# PC104.net
KiCad netlist of a schematic drawn in Altium Designer
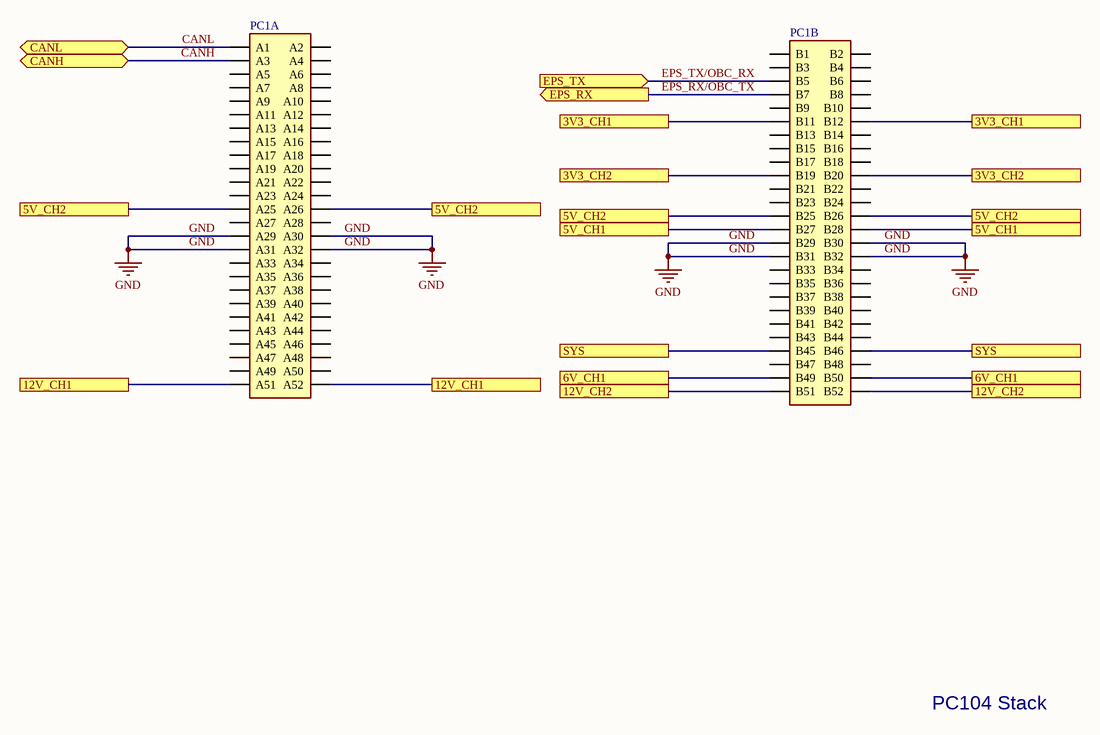
[diagram p0: PC104.SchDoc]

(export (version "E")
  (design (tool "Eeschema 10.0.6"))
  (components
    (comp (ref "PC1")
      (value "SSQ-126-21-G-D")
      (footprint "PC104 STACK HEADER")
      (description "PC104 stack header, 2.54mm 4x26positions")
      (fields (field (name "DISTRIBUTOR PART NUMBER") "SSQ-126-21-G-D-ND"))
      (libsource (lib "Ahristi_Library") (part "PC104"))
    )
  )
  (nets
    (net (code "1") (name "/3V3_CH1") (class "Default")
      (node (ref "PC1") (pin "B11") (pinfunction "B11_B11") (pintype "passive"))
      (node (ref "PC1") (pin "B12") (pinfunction "B12_B12") (pintype "passive"))
    )
    (net (code "2") (name "/3V3_CH2") (class "Default")
      (node (ref "PC1") (pin "B19") (pinfunction "B19_B19") (pintype "passive"))
      (node (ref "PC1") (pin "B20") (pinfunction "B20_B20") (pintype "passive"))
    )
    (net (code "3") (name "/5V_CH1") (class "Default")
      (node (ref "PC1") (pin "B27") (pinfunction "B27_B27") (pintype "passive"))
      (node (ref "PC1") (pin "B28") (pinfunction "B28_B28") (pintype "passive"))
    )
    (net (code "4") (name "/5V_CH2") (class "Default")
      (node (ref "PC1") (pin "A25") (pinfunction "A25_A25") (pintype "passive"))
      (node (ref "PC1") (pin "A26") (pinfunction "A26_A26") (pintype "passive"))
      (node (ref "PC1") (pin "B25") (pinfunction "B25_B25") (pintype "passive"))
      (node (ref "PC1") (pin "B26") (pinfunction "B26_B26") (pintype "passive"))
    )
    (net (code "5") (name "/6V_CH1") (class "Default")
      (node (ref "PC1") (pin "B49") (pinfunction "B49_B49") (pintype "passive"))
      (node (ref "PC1") (pin "B50") (pinfunction "B50_B50") (pintype "passive"))
    )
    (net (code "6") (name "/12V_CH1") (class "Default")
      (node (ref "PC1") (pin "A51") (pinfunction "A51_A51") (pintype "passive"))
      (node (ref "PC1") (pin "A52") (pinfunction "A52_A52") (pintype "passive"))
    )
    (net (code "7") (name "/12V_CH2") (class "Default")
      (node (ref "PC1") (pin "B51") (pinfunction "B51_B51") (pintype "passive"))
      (node (ref "PC1") (pin "B52") (pinfunction "B52_B52") (pintype "passive"))
    )
    (net (code "8") (name "/CANH") (class "Default")
      (node (ref "PC1") (pin "A3") (pinfunction "A3_A3") (pintype "passive"))
    )
    (net (code "9") (name "/CANL") (class "Default")
      (node (ref "PC1") (pin "A1") (pinfunction "A1_A1") (pintype "passive"))
    )
    (net (code "10") (name "/EPS_RX{slash}OBC_TX") (class "Default")
      (node (ref "PC1") (pin "B7") (pinfunction "B7_B7") (pintype "passive"))
    )
    (net (code "11") (name "/EPS_TX{slash}OBC_RX") (class "Default")
      (node (ref "PC1") (pin "B5") (pinfunction "B5_B5") (pintype "passive"))
    )
    (net (code "12") (name "/SYS") (class "Default")
      (node (ref "PC1") (pin "B45") (pinfunction "B45_B45") (pintype "passive"))
      (node (ref "PC1") (pin "B46") (pinfunction "B46_B46") (pintype "passive"))
    )
    (net (code "13") (name "GND") (class "Default")
      (node (ref "PC1") (pin "A29") (pinfunction "A29_A29") (pintype "passive"))
      (node (ref "PC1") (pin "A30") (pinfunction "A30_A30") (pintype "passive"))
      (node (ref "PC1") (pin "A31") (pinfunction "A31_A31") (pintype "passive"))
      (node (ref "PC1") (pin "A32") (pinfunction "A32_A32") (pintype "passive"))
      (node (ref "PC1") (pin "B29") (pinfunction "B29_B29") (pintype "passive"))
      (node (ref "PC1") (pin "B30") (pinfunction "B30_B30") (pintype "passive"))
      (node (ref "PC1") (pin "B31") (pinfunction "B31_B31") (pintype "passive"))
      (node (ref "PC1") (pin "B32") (pinfunction "B32_B32") (pintype "passive"))
    )
    (net (code "14") (name "unconnected-(PC1-PadA2)") (class "Default")
      (node (ref "PC1") (pin "A2") (pinfunction "A2_A2") (pintype "passive"))
    )
    (net (code "15") (name "unconnected-(PC1-PadA4)") (class "Default")
      (node (ref "PC1") (pin "A4") (pinfunction "A4_A4") (pintype "passive"))
    )
    (net (code "16") (name "unconnected-(PC1-PadA5)") (class "Default")
      (node (ref "PC1") (pin "A5") (pinfunction "A5_A5") (pintype "passive"))
    )
    (net (code "17") (name "unconnected-(PC1-PadA6)") (class "Default")
      (node (ref "PC1") (pin "A6") (pinfunction "A6_A6") (pintype "passive"))
    )
    (net (code "18") (name "unconnected-(PC1-PadA7)") (class "Default")
      (node (ref "PC1") (pin "A7") (pinfunction "A7_A7") (pintype "passive"))
    )
    (net (code "19") (name "unconnected-(PC1-PadA8)") (class "Default")
      (node (ref "PC1") (pin "A8") (pinfunction "A8_A8") (pintype "passive"))
    )
    (net (code "20") (name "unconnected-(PC1-PadA9)") (class "Default")
      (node (ref "PC1") (pin "A9") (pinfunction "A9_A9") (pintype "passive"))
    )
    (net (code "21") (name "unconnected-(PC1-PadA10)") (class "Default")
      (node (ref "PC1") (pin "A10") (pinfunction "A10_A10") (pintype "passive"))
    )
    (net (code "22") (name "unconnected-(PC1-PadA11)") (class "Default")
      (node (ref "PC1") (pin "A11") (pinfunction "A11_A11") (pintype "passive"))
    )
    (net (code "23") (name "unconnected-(PC1-PadA12)") (class "Default")
      (node (ref "PC1") (pin "A12") (pinfunction "A12_A12") (pintype "passive"))
    )
    (net (code "24") (name "unconnected-(PC1-PadA13)") (class "Default")
      (node (ref "PC1") (pin "A13") (pinfunction "A13_A13") (pintype "passive"))
    )
    (net (code "25") (name "unconnected-(PC1-PadA14)") (class "Default")
      (node (ref "PC1") (pin "A14") (pinfunction "A14_A14") (pintype "passive"))
    )
    (net (code "26") (name "unconnected-(PC1-PadA15)") (class "Default")
      (node (ref "PC1") (pin "A15") (pinfunction "A15_A15") (pintype "passive"))
    )
    (net (code "27") (name "unconnected-(PC1-PadA16)") (class "Default")
      (node (ref "PC1") (pin "A16") (pinfunction "A16_A16") (pintype "passive"))
    )
    (net (code "28") (name "unconnected-(PC1-PadA17)") (class "Default")
      (node (ref "PC1") (pin "A17") (pinfunction "A17_A17") (pintype "passive"))
    )
    (net (code "29") (name "unconnected-(PC1-PadA18)") (class "Default")
      (node (ref "PC1") (pin "A18") (pinfunction "A18_A18") (pintype "passive"))
    )
    (net (code "30") (name "unconnected-(PC1-PadA19)") (class "Default")
      (node (ref "PC1") (pin "A19") (pinfunction "A19_A19") (pintype "passive"))
    )
    (net (code "31") (name "unconnected-(PC1-PadA20)") (class "Default")
      (node (ref "PC1") (pin "A20") (pinfunction "A20_A20") (pintype "passive"))
    )
    (net (code "32") (name "unconnected-(PC1-PadA21)") (class "Default")
      (node (ref "PC1") (pin "A21") (pinfunction "A21_A21") (pintype "passive"))
    )
    (net (code "33") (name "unconnected-(PC1-PadA22)") (class "Default")
      (node (ref "PC1") (pin "A22") (pinfunction "A22_A22") (pintype "passive"))
    )
    (net (code "34") (name "unconnected-(PC1-PadA23)") (class "Default")
      (node (ref "PC1") (pin "A23") (pinfunction "A23_A23") (pintype "passive"))
    )
    (net (code "35") (name "unconnected-(PC1-PadA24)") (class "Default")
      (node (ref "PC1") (pin "A24") (pinfunction "A24_A24") (pintype "passive"))
    )
    (net (code "36") (name "unconnected-(PC1-PadA27)") (class "Default")
      (node (ref "PC1") (pin "A27") (pinfunction "A27_A27") (pintype "passive"))
    )
    (net (code "37") (name "unconnected-(PC1-PadA28)") (class "Default")
      (node (ref "PC1") (pin "A28") (pinfunction "A28_A28") (pintype "passive"))
    )
    (net (code "38") (name "unconnected-(PC1-PadA33)") (class "Default")
      (node (ref "PC1") (pin "A33") (pinfunction "A33_A33") (pintype "passive"))
    )
    (net (code "39") (name "unconnected-(PC1-PadA34)") (class "Default")
      (node (ref "PC1") (pin "A34") (pinfunction "A34_A34") (pintype "passive"))
    )
    (net (code "40") (name "unconnected-(PC1-PadA35)") (class "Default")
      (node (ref "PC1") (pin "A35") (pinfunction "A35_A35") (pintype "passive"))
    )
    (net (code "41") (name "unconnected-(PC1-PadA36)") (class "Default")
      (node (ref "PC1") (pin "A36") (pinfunction "A36_A36") (pintype "passive"))
    )
    (net (code "42") (name "unconnected-(PC1-PadA37)") (class "Default")
      (node (ref "PC1") (pin "A37") (pinfunction "A37_A37") (pintype "passive"))
    )
    (net (code "43") (name "unconnected-(PC1-PadA38)") (class "Default")
      (node (ref "PC1") (pin "A38") (pinfunction "A38_A38") (pintype "passive"))
    )
    (net (code "44") (name "unconnected-(PC1-PadA39)") (class "Default")
      (node (ref "PC1") (pin "A39") (pinfunction "A39_A39") (pintype "passive"))
    )
    (net (code "45") (name "unconnected-(PC1-PadA40)") (class "Default")
      (node (ref "PC1") (pin "A40") (pinfunction "A40_A40") (pintype "passive"))
    )
    (net (code "46") (name "unconnected-(PC1-PadA41)") (class "Default")
      (node (ref "PC1") (pin "A41") (pinfunction "A41_A41") (pintype "passive"))
    )
    (net (code "47") (name "unconnected-(PC1-PadA42)") (class "Default")
      (node (ref "PC1") (pin "A42") (pinfunction "A42_A42") (pintype "passive"))
    )
    (net (code "48") (name "unconnected-(PC1-PadA43)") (class "Default")
      (node (ref "PC1") (pin "A43") (pinfunction "A43_A43") (pintype "passive"))
    )
    (net (code "49") (name "unconnected-(PC1-PadA44)") (class "Default")
      (node (ref "PC1") (pin "A44") (pinfunction "A44_A44") (pintype "passive"))
    )
    (net (code "50") (name "unconnected-(PC1-PadA45)") (class "Default")
      (node (ref "PC1") (pin "A45") (pinfunction "A45_A45") (pintype "passive"))
    )
    (net (code "51") (name "unconnected-(PC1-PadA46)") (class "Default")
      (node (ref "PC1") (pin "A46") (pinfunction "A46_A46") (pintype "passive"))
    )
    (net (code "52") (name "unconnected-(PC1-PadA47)") (class "Default")
      (node (ref "PC1") (pin "A47") (pinfunction "A47_A47") (pintype "passive"))
    )
    (net (code "53") (name "unconnected-(PC1-PadA48)") (class "Default")
      (node (ref "PC1") (pin "A48") (pinfunction "A48_A48") (pintype "passive"))
    )
    (net (code "54") (name "unconnected-(PC1-PadA49)") (class "Default")
      (node (ref "PC1") (pin "A49") (pinfunction "A49_A49") (pintype "passive"))
    )
    (net (code "55") (name "unconnected-(PC1-PadA50)") (class "Default")
      (node (ref "PC1") (pin "A50") (pinfunction "A50_A50") (pintype "passive"))
    )
    (net (code "56") (name "unconnected-(PC1-PadB1)") (class "Default")
      (node (ref "PC1") (pin "B1") (pinfunction "B1_B1") (pintype "passive"))
    )
    (net (code "57") (name "unconnected-(PC1-PadB2)") (class "Default")
      (node (ref "PC1") (pin "B2") (pinfunction "B2_B2") (pintype "passive"))
    )
    (net (code "58") (name "unconnected-(PC1-PadB3)") (class "Default")
      (node (ref "PC1") (pin "B3") (pinfunction "B3_B3") (pintype "passive"))
    )
    (net (code "59") (name "unconnected-(PC1-PadB4)") (class "Default")
      (node (ref "PC1") (pin "B4") (pinfunction "B4_B4") (pintype "passive"))
    )
    (net (code "60") (name "unconnected-(PC1-PadB6)") (class "Default")
      (node (ref "PC1") (pin "B6") (pinfunction "B6_B6") (pintype "passive"))
    )
    (net (code "61") (name "unconnected-(PC1-PadB8)") (class "Default")
      (node (ref "PC1") (pin "B8") (pinfunction "B8_B8") (pintype "passive"))
    )
    (net (code "62") (name "unconnected-(PC1-PadB9)") (class "Default")
      (node (ref "PC1") (pin "B9") (pinfunction "B9_B9") (pintype "passive"))
    )
    (net (code "63") (name "unconnected-(PC1-PadB10)") (class "Default")
      (node (ref "PC1") (pin "B10") (pinfunction "B10_B10") (pintype "passive"))
    )
    (net (code "64") (name "unconnected-(PC1-PadB13)") (class "Default")
      (node (ref "PC1") (pin "B13") (pinfunction "B13_B13") (pintype "passive"))
    )
    (net (code "65") (name "unconnected-(PC1-PadB14)") (class "Default")
      (node (ref "PC1") (pin "B14") (pinfunction "B14_B14") (pintype "passive"))
    )
    (net (code "66") (name "unconnected-(PC1-PadB15)") (class "Default")
      (node (ref "PC1") (pin "B15") (pinfunction "B15_B15") (pintype "passive"))
    )
    (net (code "67") (name "unconnected-(PC1-PadB16)") (class "Default")
      (node (ref "PC1") (pin "B16") (pinfunction "B16_B16") (pintype "passive"))
    )
    (net (code "68") (name "unconnected-(PC1-PadB17)") (class "Default")
      (node (ref "PC1") (pin "B17") (pinfunction "B17_B17") (pintype "passive"))
    )
    (net (code "69") (name "unconnected-(PC1-PadB18)") (class "Default")
      (node (ref "PC1") (pin "B18") (pinfunction "B18_B18") (pintype "passive"))
    )
    (net (code "70") (name "unconnected-(PC1-PadB21)") (class "Default")
      (node (ref "PC1") (pin "B21") (pinfunction "B21_B21") (pintype "passive"))
    )
    (net (code "71") (name "unconnected-(PC1-PadB22)") (class "Default")
      (node (ref "PC1") (pin "B22") (pinfunction "B22_B22") (pintype "passive"))
    )
    (net (code "72") (name "unconnected-(PC1-PadB23)") (class "Default")
      (node (ref "PC1") (pin "B23") (pinfunction "B23_B23") (pintype "passive"))
    )
    (net (code "73") (name "unconnected-(PC1-PadB24)") (class "Default")
      (node (ref "PC1") (pin "B24") (pinfunction "B24_B24") (pintype "passive"))
    )
    (net (code "74") (name "unconnected-(PC1-PadB33)") (class "Default")
      (node (ref "PC1") (pin "B33") (pinfunction "B33_B33") (pintype "passive"))
    )
    (net (code "75") (name "unconnected-(PC1-PadB34)") (class "Default")
      (node (ref "PC1") (pin "B34") (pinfunction "B34_B34") (pintype "passive"))
    )
    (net (code "76") (name "unconnected-(PC1-PadB35)") (class "Default")
      (node (ref "PC1") (pin "B35") (pinfunction "B35_B35") (pintype "passive"))
    )
    (net (code "77") (name "unconnected-(PC1-PadB36)") (class "Default")
      (node (ref "PC1") (pin "B36") (pinfunction "B36_B36") (pintype "passive"))
    )
    (net (code "78") (name "unconnected-(PC1-PadB37)") (class "Default")
      (node (ref "PC1") (pin "B37") (pinfunction "B37_B37") (pintype "passive"))
    )
    (net (code "79") (name "unconnected-(PC1-PadB38)") (class "Default")
      (node (ref "PC1") (pin "B38") (pinfunction "B38_B38") (pintype "passive"))
    )
    (net (code "80") (name "unconnected-(PC1-PadB39)") (class "Default")
      (node (ref "PC1") (pin "B39") (pinfunction "B39_B39") (pintype "passive"))
    )
    (net (code "81") (name "unconnected-(PC1-PadB40)") (class "Default")
      (node (ref "PC1") (pin "B40") (pinfunction "B40_B40") (pintype "passive"))
    )
    (net (code "82") (name "unconnected-(PC1-PadB41)") (class "Default")
      (node (ref "PC1") (pin "B41") (pinfunction "B41_B41") (pintype "passive"))
    )
    (net (code "83") (name "unconnected-(PC1-PadB42)") (class "Default")
      (node (ref "PC1") (pin "B42") (pinfunction "B42_B42") (pintype "passive"))
    )
    (net (code "84") (name "unconnected-(PC1-PadB43)") (class "Default")
      (node (ref "PC1") (pin "B43") (pinfunction "B43_B43") (pintype "passive"))
    )
    (net (code "85") (name "unconnected-(PC1-PadB44)") (class "Default")
      (node (ref "PC1") (pin "B44") (pinfunction "B44_B44") (pintype "passive"))
    )
    (net (code "86") (name "unconnected-(PC1-PadB47)") (class "Default")
      (node (ref "PC1") (pin "B47") (pinfunction "B47_B47") (pintype "passive"))
    )
    (net (code "87") (name "unconnected-(PC1-PadB48)") (class "Default")
      (node (ref "PC1") (pin "B48") (pinfunction "B48_B48") (pintype "passive"))
    )
  )
)
